# Inputs.net
KiCad netlist of a schematic drawn in Altium Designer
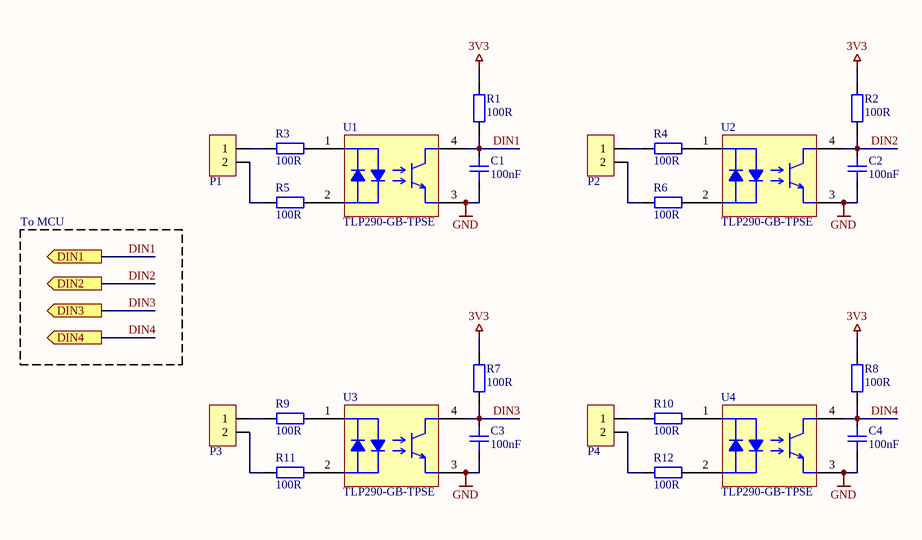
[diagram p0: Inputs.SchDoc]

(export (version "E")
  (design (tool "Eeschema 10.0.6"))
  (components
    (comp (ref "C1")
      (value "100nF")
      (footprint "AG.Passive:C0805")
      (description "Generic Capacitor")
      (fields (field (name "TOLERANCE") "20%"))
      (libsource (lib "AG.Generic") (part "C"))
    )
    (comp (ref "C2")
      (value "100nF")
      (footprint "AG.Passive:C0805")
      (description "Generic Capacitor")
      (fields (field (name "TOLERANCE") "20%"))
      (libsource (lib "AG.Generic") (part "C"))
    )
    (comp (ref "C3")
      (value "100nF")
      (footprint "AG.Passive:C0805")
      (description "Generic Capacitor")
      (fields (field (name "TOLERANCE") "20%"))
      (libsource (lib "AG.Generic") (part "C"))
    )
    (comp (ref "C4")
      (value "100nF")
      (footprint "AG.Passive:C0805")
      (description "Generic Capacitor")
      (fields (field (name "TOLERANCE") "20%"))
      (libsource (lib "AG.Generic") (part "C"))
    )
    (comp (ref "P1")
      (value "PINHDR_2x1")
      (footprint "AG.Connectors:HEADER-2.54-2P1")
      (description "Generic Pin Header 2x1")
      (libsource (lib "AG.Connectors") (part "PINHDR_2x1"))
    )
    (comp (ref "P2")
      (value "PINHDR_2x1")
      (footprint "AG.Connectors:HEADER-2.54-2P1")
      (description "Generic Pin Header 2x1")
      (libsource (lib "AG.Connectors") (part "PINHDR_2x1"))
    )
    (comp (ref "P3")
      (value "PINHDR_2x1")
      (footprint "AG.Connectors:HEADER-2.54-2P1")
      (description "Generic Pin Header 2x1")
      (libsource (lib "AG.Connectors") (part "PINHDR_2x1"))
    )
    (comp (ref "P4")
      (value "PINHDR_2x1")
      (footprint "AG.Connectors:HEADER-2.54-2P1")
      (description "Generic Pin Header 2x1")
      (libsource (lib "AG.Connectors") (part "PINHDR_2x1"))
    )
    (comp (ref "R1")
      (value "100R")
      (footprint "AG.Passive:R0805")
      (description "Generic Resistor")
      (fields (field (name "TOLERANCE") "1%"))
      (libsource (lib "AG.Generic") (part "R"))
    )
    (comp (ref "R2")
      (value "100R")
      (footprint "AG.Passive:R0805")
      (description "Generic Resistor")
      (fields (field (name "TOLERANCE") "1%"))
      (libsource (lib "AG.Generic") (part "R"))
    )
    (comp (ref "R3")
      (value "100R")
      (footprint "AG.Passive:R0805")
      (description "Generic Resistor")
      (fields (field (name "TOLERANCE") "1%"))
      (libsource (lib "AG.Generic") (part "R"))
    )
    (comp (ref "R4")
      (value "100R")
      (footprint "AG.Passive:R0805")
      (description "Generic Resistor")
      (fields (field (name "TOLERANCE") "1%"))
      (libsource (lib "AG.Generic") (part "R"))
    )
    (comp (ref "R5")
      (value "100R")
      (footprint "AG.Passive:R0805")
      (description "Generic Resistor")
      (fields (field (name "TOLERANCE") "1%"))
      (libsource (lib "AG.Generic") (part "R"))
    )
    (comp (ref "R6")
      (value "100R")
      (footprint "AG.Passive:R0805")
      (description "Generic Resistor")
      (fields (field (name "TOLERANCE") "1%"))
      (libsource (lib "AG.Generic") (part "R"))
    )
    (comp (ref "R7")
      (value "100R")
      (footprint "AG.Passive:R0805")
      (description "Generic Resistor")
      (fields (field (name "TOLERANCE") "1%"))
      (libsource (lib "AG.Generic") (part "R"))
    )
    (comp (ref "R8")
      (value "100R")
      (footprint "AG.Passive:R0805")
      (description "Generic Resistor")
      (fields (field (name "TOLERANCE") "1%"))
      (libsource (lib "AG.Generic") (part "R"))
    )
    (comp (ref "R9")
      (value "100R")
      (footprint "AG.Passive:R0805")
      (description "Generic Resistor")
      (fields (field (name "TOLERANCE") "1%"))
      (libsource (lib "AG.Generic") (part "R"))
    )
    (comp (ref "R10")
      (value "100R")
      (footprint "AG.Passive:R0805")
      (description "Generic Resistor")
      (fields (field (name "TOLERANCE") "1%"))
      (libsource (lib "AG.Generic") (part "R"))
    )
    (comp (ref "R11")
      (value "100R")
      (footprint "AG.Passive:R0805")
      (description "Generic Resistor")
      (fields (field (name "TOLERANCE") "1%"))
      (libsource (lib "AG.Generic") (part "R"))
    )
    (comp (ref "R12")
      (value "100R")
      (footprint "AG.Passive:R0805")
      (description "Generic Resistor")
      (fields (field (name "TOLERANCE") "1%"))
      (libsource (lib "AG.Generic") (part "R"))
    )
    (comp (ref "U1")
      (value "TLP290-GB-TPSE")
      (footprint "AG:SO-4-SOIC127P600-8N")
      (description "OPTOISOLATOR 3.75KV TRANS 4-SO")
      (libsource (lib "AG") (part "TLP290-GB-TPSE"))
    )
    (comp (ref "U2")
      (value "TLP290-GB-TPSE")
      (footprint "AG:SO-4-SOIC127P600-8N")
      (description "OPTOISOLATOR 3.75KV TRANS 4-SO")
      (libsource (lib "AG") (part "TLP290-GB-TPSE"))
    )
    (comp (ref "U3")
      (value "TLP290-GB-TPSE")
      (footprint "AG:SO-4-SOIC127P600-8N")
      (description "OPTOISOLATOR 3.75KV TRANS 4-SO")
      (libsource (lib "AG") (part "TLP290-GB-TPSE"))
    )
    (comp (ref "U4")
      (value "TLP290-GB-TPSE")
      (footprint "AG:SO-4-SOIC127P600-8N")
      (description "OPTOISOLATOR 3.75KV TRANS 4-SO")
      (libsource (lib "AG") (part "TLP290-GB-TPSE"))
    )
  )
  (nets
    (net (code "1") (name "/DIN1") (class "Default")
      (node (ref "C1") (pin "2") (pinfunction "2_2") (pintype "passive"))
      (node (ref "R1") (pin "2") (pintype "passive"))
      (node (ref "U1") (pin "4") (pinfunction "4_4") (pintype "passive"))
    )
    (net (code "2") (name "/DIN2") (class "Default")
      (node (ref "C2") (pin "2") (pinfunction "2_2") (pintype "passive"))
      (node (ref "R2") (pin "2") (pintype "passive"))
      (node (ref "U2") (pin "4") (pinfunction "4_4") (pintype "passive"))
    )
    (net (code "3") (name "/DIN3") (class "Default")
      (node (ref "C3") (pin "2") (pinfunction "2_2") (pintype "passive"))
      (node (ref "R7") (pin "2") (pintype "passive"))
      (node (ref "U3") (pin "4") (pinfunction "4_4") (pintype "passive"))
    )
    (net (code "4") (name "/DIN4") (class "Default")
      (node (ref "C4") (pin "2") (pinfunction "2_2") (pintype "passive"))
      (node (ref "R8") (pin "2") (pintype "passive"))
      (node (ref "U4") (pin "4") (pinfunction "4_4") (pintype "passive"))
    )
    (net (code "5") (name "3V3") (class "Default")
      (node (ref "R1") (pin "1") (pintype "passive"))
      (node (ref "R2") (pin "1") (pintype "passive"))
      (node (ref "R7") (pin "1") (pintype "passive"))
      (node (ref "R8") (pin "1") (pintype "passive"))
    )
    (net (code "6") (name "GND") (class "Default")
      (node (ref "C1") (pin "1") (pinfunction "1_1") (pintype "passive"))
      (node (ref "C2") (pin "1") (pinfunction "1_1") (pintype "passive"))
      (node (ref "C3") (pin "1") (pinfunction "1_1") (pintype "passive"))
      (node (ref "C4") (pin "1") (pinfunction "1_1") (pintype "passive"))
      (node (ref "U1") (pin "3") (pinfunction "3_3") (pintype "passive"))
      (node (ref "U2") (pin "3") (pinfunction "3_3") (pintype "passive"))
      (node (ref "U3") (pin "3") (pinfunction "3_3") (pintype "passive"))
      (node (ref "U4") (pin "3") (pinfunction "3_3") (pintype "passive"))
    )
    (net (code "7") (name "Net-(P1-Pad1)") (class "Default")
      (node (ref "P1") (pin "1") (pinfunction "1_1") (pintype "passive"))
      (node (ref "R3") (pin "2") (pintype "passive"))
    )
    (net (code "8") (name "Net-(P1-Pad2)") (class "Default")
      (node (ref "P1") (pin "2") (pinfunction "2_2") (pintype "passive"))
      (node (ref "R5") (pin "2") (pintype "passive"))
    )
    (net (code "9") (name "Net-(P2-Pad1)") (class "Default")
      (node (ref "P2") (pin "1") (pinfunction "1_1") (pintype "passive"))
      (node (ref "R4") (pin "2") (pintype "passive"))
    )
    (net (code "10") (name "Net-(P2-Pad2)") (class "Default")
      (node (ref "P2") (pin "2") (pinfunction "2_2") (pintype "passive"))
      (node (ref "R6") (pin "2") (pintype "passive"))
    )
    (net (code "11") (name "Net-(P3-Pad1)") (class "Default")
      (node (ref "P3") (pin "1") (pinfunction "1_1") (pintype "passive"))
      (node (ref "R9") (pin "2") (pintype "passive"))
    )
    (net (code "12") (name "Net-(P3-Pad2)") (class "Default")
      (node (ref "P3") (pin "2") (pinfunction "2_2") (pintype "passive"))
      (node (ref "R11") (pin "2") (pintype "passive"))
    )
    (net (code "13") (name "Net-(P4-Pad1)") (class "Default")
      (node (ref "P4") (pin "1") (pinfunction "1_1") (pintype "passive"))
      (node (ref "R10") (pin "2") (pintype "passive"))
    )
    (net (code "14") (name "Net-(P4-Pad2)") (class "Default")
      (node (ref "P4") (pin "2") (pinfunction "2_2") (pintype "passive"))
      (node (ref "R12") (pin "2") (pintype "passive"))
    )
    (net (code "15") (name "Net-(R3-Pad1)") (class "Default")
      (node (ref "R3") (pin "1") (pintype "passive"))
      (node (ref "U1") (pin "1") (pinfunction "1_1") (pintype "passive"))
    )
    (net (code "16") (name "Net-(R4-Pad1)") (class "Default")
      (node (ref "R4") (pin "1") (pintype "passive"))
      (node (ref "U2") (pin "1") (pinfunction "1_1") (pintype "passive"))
    )
    (net (code "17") (name "Net-(R5-Pad1)") (class "Default")
      (node (ref "R5") (pin "1") (pintype "passive"))
      (node (ref "U1") (pin "2") (pinfunction "2_2") (pintype "passive"))
    )
    (net (code "18") (name "Net-(R6-Pad1)") (class "Default")
      (node (ref "R6") (pin "1") (pintype "passive"))
      (node (ref "U2") (pin "2") (pinfunction "2_2") (pintype "passive"))
    )
    (net (code "19") (name "Net-(R9-Pad1)") (class "Default")
      (node (ref "R9") (pin "1") (pintype "passive"))
      (node (ref "U3") (pin "1") (pinfunction "1_1") (pintype "passive"))
    )
    (net (code "20") (name "Net-(R10-Pad1)") (class "Default")
      (node (ref "R10") (pin "1") (pintype "passive"))
      (node (ref "U4") (pin "1") (pinfunction "1_1") (pintype "passive"))
    )
    (net (code "21") (name "Net-(R11-Pad1)") (class "Default")
      (node (ref "R11") (pin "1") (pintype "passive"))
      (node (ref "U3") (pin "2") (pinfunction "2_2") (pintype "passive"))
    )
    (net (code "22") (name "Net-(R12-Pad1)") (class "Default")
      (node (ref "R12") (pin "1") (pintype "passive"))
      (node (ref "U4") (pin "2") (pinfunction "2_2") (pintype "passive"))
    )
  )
)
